# 477part.net
KiCad netlist of a schematic drawn in EAGLE
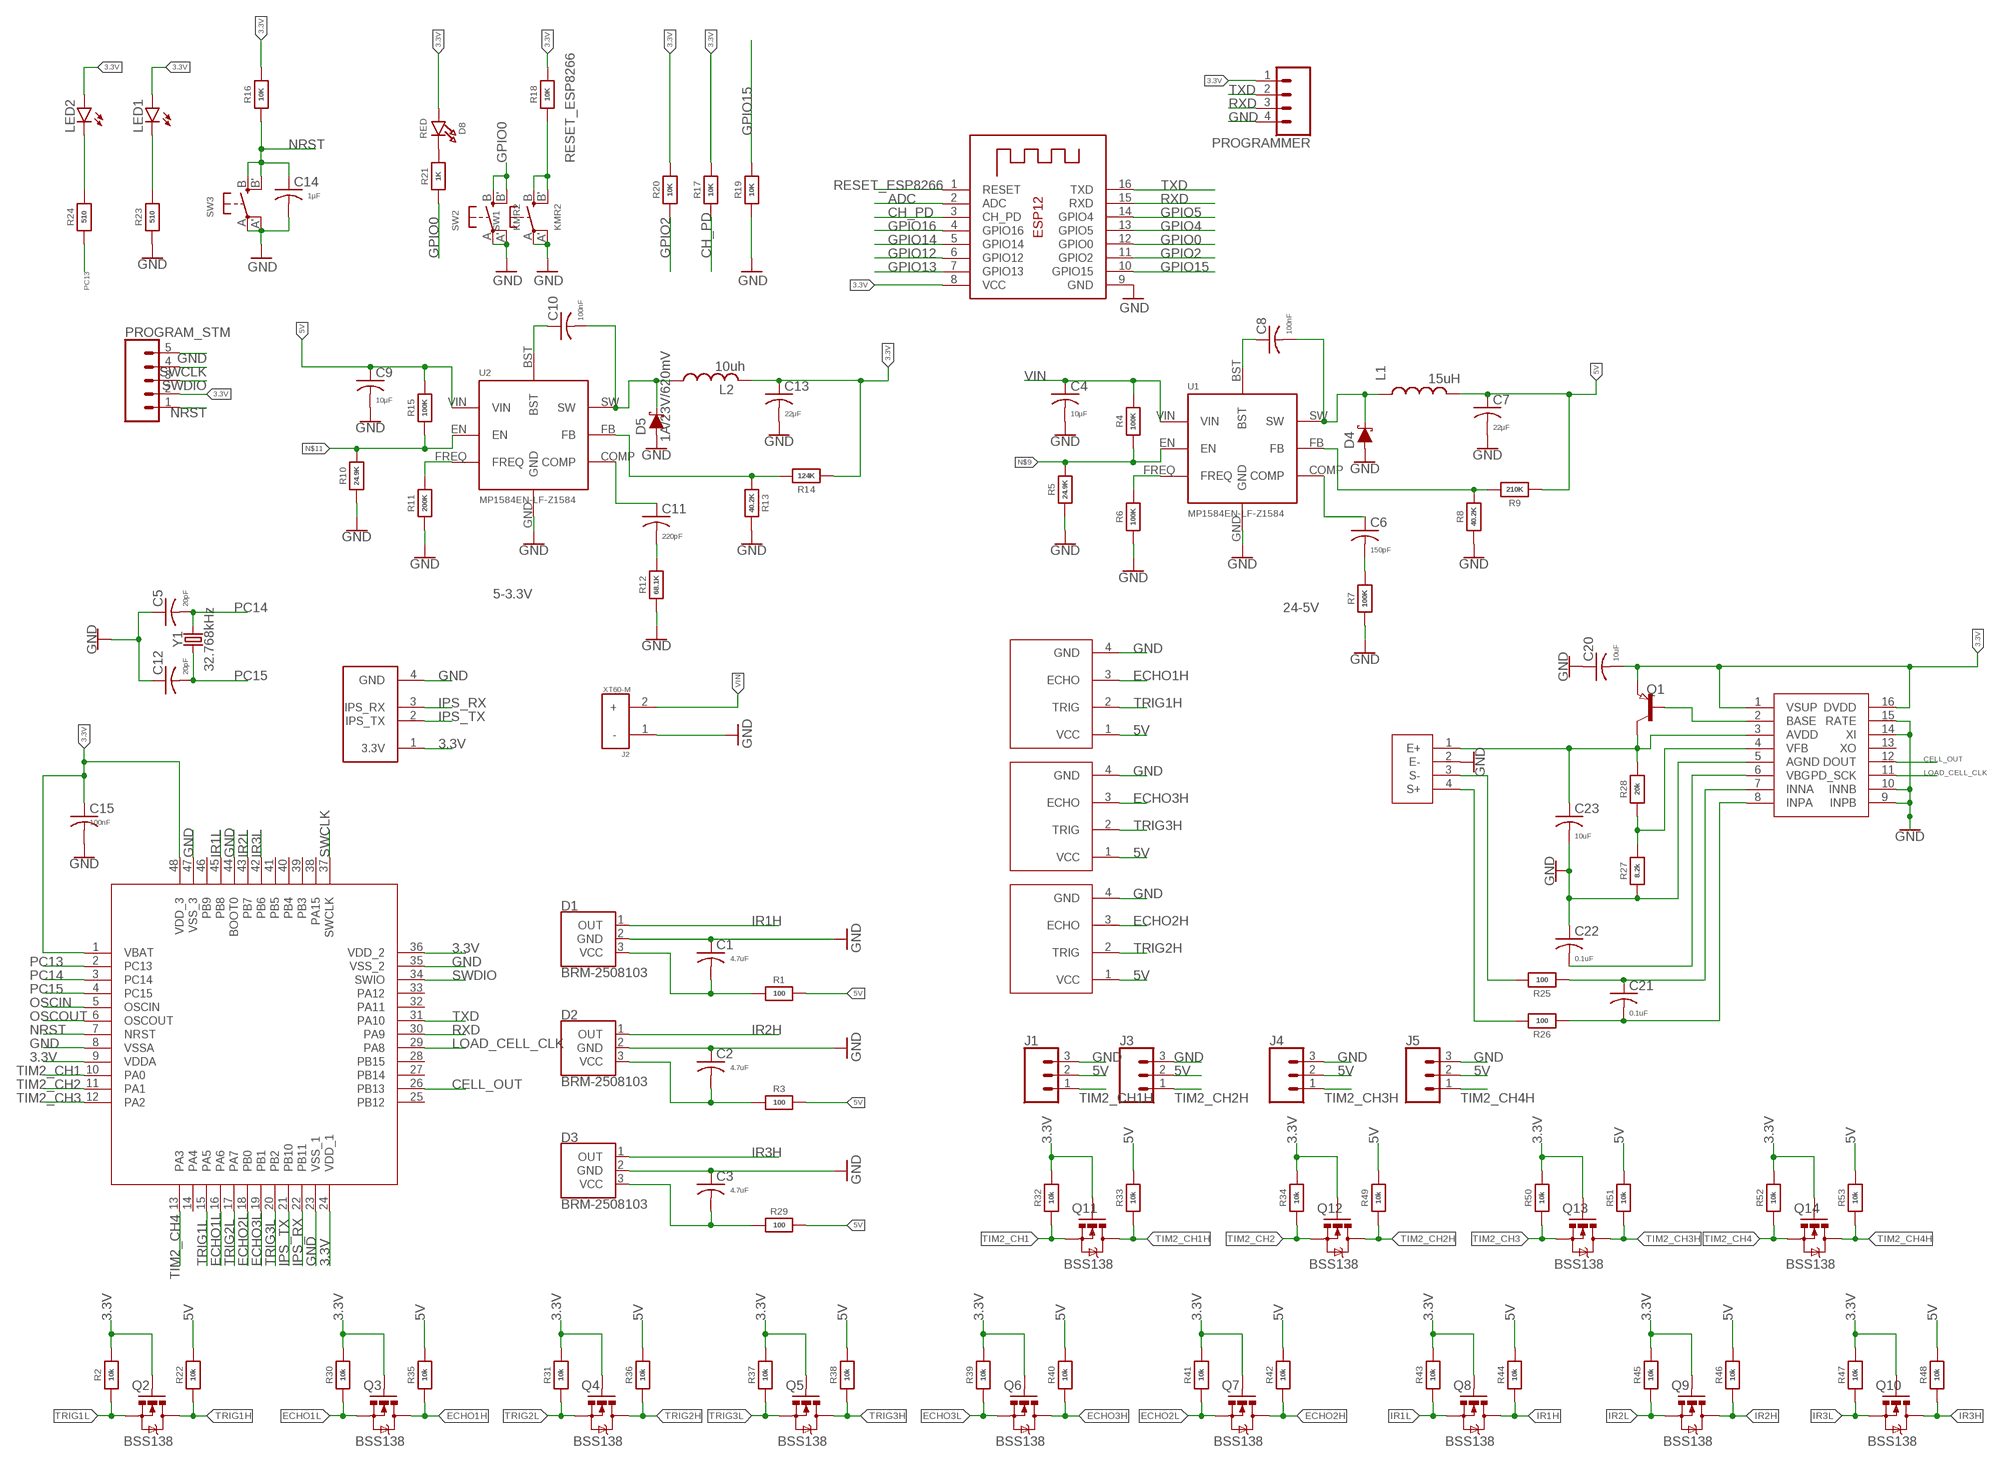
[diagram p0: schematic, sheet 1]

(export (version "E")
  (design (tool "Eeschema 10.0.6"))
  (components
    (comp (ref "C1")
      (value "4.7uF")
      (footprint "eagle-import:C0603")
      (libsource (lib "eagle-import") (part "C-USC0603"))
    )
    (comp (ref "C2")
      (value "4.7uF")
      (footprint "eagle-import:C0603")
      (libsource (lib "eagle-import") (part "C-USC0603"))
    )
    (comp (ref "C3")
      (value "4.7uF")
      (footprint "eagle-import:C0603")
      (libsource (lib "eagle-import") (part "C-USC0603"))
    )
    (comp (ref "C4")
      (value "10μF")
      (footprint "eagle-import:C0603")
      (libsource (lib "eagle-import") (part "C-USC0603"))
    )
    (comp (ref "C5")
      (value "20pF")
      (footprint "eagle-import:C0603")
      (libsource (lib "eagle-import") (part "C-USC0603"))
    )
    (comp (ref "C6")
      (value "150pF")
      (footprint "eagle-import:C0603")
      (libsource (lib "eagle-import") (part "C-USC0603"))
    )
    (comp (ref "C7")
      (value "22μF")
      (footprint "eagle-import:C0603")
      (libsource (lib "eagle-import") (part "C-USC0603"))
    )
    (comp (ref "C8")
      (value "100nF")
      (footprint "eagle-import:C0603")
      (libsource (lib "eagle-import") (part "C-USC0603"))
    )
    (comp (ref "C9")
      (value "10μF")
      (footprint "eagle-import:C0603")
      (libsource (lib "eagle-import") (part "C-USC0603"))
    )
    (comp (ref "C10")
      (value "100nF")
      (footprint "eagle-import:C0603")
      (libsource (lib "eagle-import") (part "C-USC0603"))
    )
    (comp (ref "C11")
      (value "220pF")
      (footprint "eagle-import:C0603")
      (libsource (lib "eagle-import") (part "C-USC0603"))
    )
    (comp (ref "C12")
      (value "20pF")
      (footprint "eagle-import:C0603")
      (libsource (lib "eagle-import") (part "C-USC0603"))
    )
    (comp (ref "C13")
      (value "22μF")
      (footprint "eagle-import:C0603")
      (libsource (lib "eagle-import") (part "C-USC0603"))
    )
    (comp (ref "C14")
      (value "1µF")
      (footprint "eagle-import:C0603")
      (libsource (lib "eagle-import") (part "C-USC0603"))
    )
    (comp (ref "C15")
      (value "100nF")
      (footprint "eagle-import:C0603")
      (libsource (lib "eagle-import") (part "C-USC0603"))
    )
    (comp (ref "C20")
      (value "10uF")
      (footprint "eagle-import:C0603")
      (libsource (lib "eagle-import") (part "C-USC0603"))
    )
    (comp (ref "C21")
      (value "0.1uF")
      (footprint "eagle-import:C0603")
      (libsource (lib "eagle-import") (part "C-USC0603"))
    )
    (comp (ref "C22")
      (value "0.1uF")
      (footprint "eagle-import:C0603")
      (libsource (lib "eagle-import") (part "C-USC0603"))
    )
    (comp (ref "C23")
      (value "10uF")
      (footprint "eagle-import:C0603")
      (libsource (lib "eagle-import") (part "C-USC0603"))
    )
    (comp (ref "D1")
      (value "BRM-2508103")
      (footprint "eagle-import:1X03")
      (libsource (lib "eagle-import") (part "BRM-2508103"))
    )
    (comp (ref "D2")
      (value "BRM-2508103")
      (footprint "eagle-import:1X03")
      (libsource (lib "eagle-import") (part "BRM-2508103"))
    )
    (comp (ref "D3")
      (value "BRM-2508103")
      (footprint "eagle-import:1X03")
      (libsource (lib "eagle-import") (part "BRM-2508103"))
    )
    (comp (ref "D4")
      (value "1A/23V/620mV")
      (footprint "eagle-import:SOD-323")
      (libsource (lib "eagle-import") (part "DIODE-SCHOTTKY-BAT20J"))
    )
    (comp (ref "D5")
      (value "1A/23V/620mV")
      (footprint "eagle-import:SOD-323")
      (libsource (lib "eagle-import") (part "DIODE-SCHOTTKY-BAT20J"))
    )
    (comp (ref "D8")
      (value "RED")
      (footprint "eagle-import:CHIPLED_0805_NOOUTLINE")
      (libsource (lib "eagle-import") (part "LED0805_NOOUTLINE"))
    )
    (comp (ref "ESP8266")
      (value "ESP-8266")
      (footprint "eagle-import:ESP-12")
      (libsource (lib "eagle-import") (part "ESP-12"))
    )
    (comp (ref "HC_SR04_1")
      (value "ULTRA_4")
      (footprint "eagle-import:1X04")
      (libsource (lib "eagle-import") (part "ULTRA_4"))
    )
    (comp (ref "HC_SR04_2")
      (value "ULTRA_4")
      (footprint "eagle-import:1X04")
      (libsource (lib "eagle-import") (part "ULTRA_4"))
    )
    (comp (ref "HC_SR04_3")
      (value "ULTRA_4")
      (footprint "eagle-import:1X04")
      (libsource (lib "eagle-import") (part "ULTRA_4"))
    )
    (comp (ref "J1")
      (value "CONN_03")
      (footprint "eagle-import:1X03")
      (libsource (lib "eagle-import") (part "CONN_03"))
    )
    (comp (ref "J2")
      (value "XT60-M")
      (footprint "eagle-import:AMASS_XT60-M")
      (fields (field (name "MF") "AMASS"))
      (libsource (lib "eagle-import") (part "XT60-M"))
    )
    (comp (ref "J3")
      (value "CONN_03")
      (footprint "eagle-import:1X03")
      (libsource (lib "eagle-import") (part "CONN_03"))
    )
    (comp (ref "J4")
      (value "CONN_03")
      (footprint "eagle-import:1X03")
      (libsource (lib "eagle-import") (part "CONN_03"))
    )
    (comp (ref "J5")
      (value "CONN_03")
      (footprint "eagle-import:1X03")
      (libsource (lib "eagle-import") (part "CONN_03"))
    )
    (comp (ref "L1")
      (value "15uH")
      (footprint "eagle-import:INDUCTOR2")
      (libsource (lib "eagle-import") (part "INDUCTOR2"))
    )
    (comp (ref "L2")
      (value "10uh")
      (footprint "eagle-import:INDUCTOR")
      (libsource (lib "eagle-import") (part "INDUCTOR"))
    )
    (comp (ref "LED1")
      (value "LEDCHIP-LED0603")
      (footprint "eagle-import:CHIP-LED0603")
      (libsource (lib "eagle-import") (part "LEDCHIP-LED0603"))
    )
    (comp (ref "LED2")
      (value "LEDCHIP-LED0603")
      (footprint "eagle-import:CHIP-LED0603")
      (libsource (lib "eagle-import") (part "LEDCHIP-LED0603"))
    )
    (comp (ref "PROGRAMMER")
      (value "CONN_04")
      (footprint "eagle-import:1X04")
      (libsource (lib "eagle-import") (part "CONN_04"))
    )
    (comp (ref "PROGRAM_STM")
      (value "CONN_05")
      (footprint "eagle-import:1X05")
      (libsource (lib "eagle-import") (part "CONN_05"))
    )
    (comp (ref "Q1")
      (value "PNP-TRANSISTOR_SOT23")
      (footprint "eagle-import:SOT23")
      (libsource (lib "eagle-import") (part "PNP-TRANSISTOR_SOT23"))
    )
    (comp (ref "Q2")
      (value "BSS138")
      (footprint "eagle-import:SOT23-3")
      (libsource (lib "eagle-import") (part "MOSFET-NCHANNELSMD"))
    )
    (comp (ref "Q3")
      (value "BSS138")
      (footprint "eagle-import:SOT23-3")
      (libsource (lib "eagle-import") (part "MOSFET-NCHANNELSMD"))
    )
    (comp (ref "Q4")
      (value "BSS138")
      (footprint "eagle-import:SOT23-3")
      (libsource (lib "eagle-import") (part "MOSFET-NCHANNELSMD"))
    )
    (comp (ref "Q5")
      (value "BSS138")
      (footprint "eagle-import:SOT23-3")
      (libsource (lib "eagle-import") (part "MOSFET-NCHANNELSMD"))
    )
    (comp (ref "Q6")
      (value "BSS138")
      (footprint "eagle-import:SOT23-3")
      (libsource (lib "eagle-import") (part "MOSFET-NCHANNELSMD"))
    )
    (comp (ref "Q7")
      (value "BSS138")
      (footprint "eagle-import:SOT23-3")
      (libsource (lib "eagle-import") (part "MOSFET-NCHANNELSMD"))
    )
    (comp (ref "Q8")
      (value "BSS138")
      (footprint "eagle-import:SOT23-3")
      (libsource (lib "eagle-import") (part "MOSFET-NCHANNELSMD"))
    )
    (comp (ref "Q9")
      (value "BSS138")
      (footprint "eagle-import:SOT23-3")
      (libsource (lib "eagle-import") (part "MOSFET-NCHANNELSMD"))
    )
    (comp (ref "Q10")
      (value "BSS138")
      (footprint "eagle-import:SOT23-3")
      (libsource (lib "eagle-import") (part "MOSFET-NCHANNELSMD"))
    )
    (comp (ref "Q11")
      (value "BSS138")
      (footprint "eagle-import:SOT23-3")
      (libsource (lib "eagle-import") (part "MOSFET-NCHANNELSMD"))
    )
    (comp (ref "Q12")
      (value "BSS138")
      (footprint "eagle-import:SOT23-3")
      (libsource (lib "eagle-import") (part "MOSFET-NCHANNELSMD"))
    )
    (comp (ref "Q13")
      (value "BSS138")
      (footprint "eagle-import:SOT23-3")
      (libsource (lib "eagle-import") (part "MOSFET-NCHANNELSMD"))
    )
    (comp (ref "Q14")
      (value "BSS138")
      (footprint "eagle-import:SOT23-3")
      (libsource (lib "eagle-import") (part "MOSFET-NCHANNELSMD"))
    )
    (comp (ref "R1")
      (value "100")
      (footprint "eagle-import:0805-NO")
      (libsource (lib "eagle-import") (part "RESISTOR0805_NOOUTLINE"))
    )
    (comp (ref "R2")
      (value "10k")
      (footprint "eagle-import:0805-NO")
      (libsource (lib "eagle-import") (part "RESISTOR0805_NOOUTLINE"))
    )
    (comp (ref "R3")
      (value "100")
      (footprint "eagle-import:0805-NO")
      (libsource (lib "eagle-import") (part "RESISTOR0805_NOOUTLINE"))
    )
    (comp (ref "R4")
      (value "100K")
      (footprint "eagle-import:0805-NO")
      (libsource (lib "eagle-import") (part "RESISTOR0805_NOOUTLINE"))
    )
    (comp (ref "R5")
      (value "24.9K")
      (footprint "eagle-import:0805-NO")
      (libsource (lib "eagle-import") (part "RESISTOR0805_NOOUTLINE"))
    )
    (comp (ref "R6")
      (value "100K")
      (footprint "eagle-import:0805-NO")
      (libsource (lib "eagle-import") (part "RESISTOR0805_NOOUTLINE"))
    )
    (comp (ref "R7")
      (value "100K")
      (footprint "eagle-import:0805-NO")
      (libsource (lib "eagle-import") (part "RESISTOR0805_NOOUTLINE"))
    )
    (comp (ref "R8")
      (value "40.2K")
      (footprint "eagle-import:0805-NO")
      (libsource (lib "eagle-import") (part "RESISTOR0805_NOOUTLINE"))
    )
    (comp (ref "R9")
      (value "210K")
      (footprint "eagle-import:0805-NO")
      (libsource (lib "eagle-import") (part "RESISTOR0805_NOOUTLINE"))
    )
    (comp (ref "R10")
      (value "24.9K")
      (footprint "eagle-import:0805-NO")
      (libsource (lib "eagle-import") (part "RESISTOR0805_NOOUTLINE"))
    )
    (comp (ref "R11")
      (value "200K")
      (footprint "eagle-import:0805-NO")
      (libsource (lib "eagle-import") (part "RESISTOR0805_NOOUTLINE"))
    )
    (comp (ref "R12")
      (value "68.1K")
      (footprint "eagle-import:0805-NO")
      (libsource (lib "eagle-import") (part "RESISTOR0805_NOOUTLINE"))
    )
    (comp (ref "R13")
      (value "40.2K")
      (footprint "eagle-import:0805-NO")
      (libsource (lib "eagle-import") (part "RESISTOR0805_NOOUTLINE"))
    )
    (comp (ref "R14")
      (value "124K")
      (footprint "eagle-import:0805-NO")
      (libsource (lib "eagle-import") (part "RESISTOR0805_NOOUTLINE"))
    )
    (comp (ref "R15")
      (value "100K")
      (footprint "eagle-import:0805-NO")
      (libsource (lib "eagle-import") (part "RESISTOR0805_NOOUTLINE"))
    )
    (comp (ref "R16")
      (value "10K")
      (footprint "eagle-import:0805-NO")
      (libsource (lib "eagle-import") (part "RESISTOR0805_NOOUTLINE"))
    )
    (comp (ref "R17")
      (value "10K")
      (footprint "eagle-import:0805-NO")
      (libsource (lib "eagle-import") (part "RESISTOR0805_NOOUTLINE"))
    )
    (comp (ref "R18")
      (value "10K")
      (footprint "eagle-import:0805-NO")
      (libsource (lib "eagle-import") (part "RESISTOR0805_NOOUTLINE"))
    )
    (comp (ref "R19")
      (value "10K")
      (footprint "eagle-import:0805-NO")
      (libsource (lib "eagle-import") (part "RESISTOR0805_NOOUTLINE"))
    )
    (comp (ref "R20")
      (value "10K")
      (footprint "eagle-import:0805-NO")
      (libsource (lib "eagle-import") (part "RESISTOR0805_NOOUTLINE"))
    )
    (comp (ref "R21")
      (value "1K")
      (footprint "eagle-import:0805-NO")
      (libsource (lib "eagle-import") (part "RESISTOR0805_NOOUTLINE"))
    )
    (comp (ref "R22")
      (value "10k")
      (footprint "eagle-import:0805-NO")
      (libsource (lib "eagle-import") (part "RESISTOR0805_NOOUTLINE"))
    )
    (comp (ref "R23")
      (value "510")
      (footprint "eagle-import:0805-NO")
      (libsource (lib "eagle-import") (part "RESISTOR0805_NOOUTLINE"))
    )
    (comp (ref "R24")
      (value "510")
      (footprint "eagle-import:0805-NO")
      (libsource (lib "eagle-import") (part "RESISTOR0805_NOOUTLINE"))
    )
    (comp (ref "R25")
      (value "100")
      (footprint "eagle-import:0805-NO")
      (libsource (lib "eagle-import") (part "RESISTOR0805_NOOUTLINE"))
    )
    (comp (ref "R26")
      (value "100")
      (footprint "eagle-import:0805-NO")
      (libsource (lib "eagle-import") (part "RESISTOR0805_NOOUTLINE"))
    )
    (comp (ref "R27")
      (value "8.2k")
      (footprint "eagle-import:0805-NO")
      (libsource (lib "eagle-import") (part "RESISTOR0805_NOOUTLINE"))
    )
    (comp (ref "R28")
      (value "20k")
      (footprint "eagle-import:0805-NO")
      (libsource (lib "eagle-import") (part "RESISTOR0805_NOOUTLINE"))
    )
    (comp (ref "R29")
      (value "100")
      (footprint "eagle-import:0805-NO")
      (libsource (lib "eagle-import") (part "RESISTOR0805_NOOUTLINE"))
    )
    (comp (ref "R30")
      (value "10k")
      (footprint "eagle-import:0805-NO")
      (libsource (lib "eagle-import") (part "RESISTOR0805_NOOUTLINE"))
    )
    (comp (ref "R31")
      (value "10k")
      (footprint "eagle-import:0805-NO")
      (libsource (lib "eagle-import") (part "RESISTOR0805_NOOUTLINE"))
    )
    (comp (ref "R32")
      (value "10k")
      (footprint "eagle-import:0805-NO")
      (libsource (lib "eagle-import") (part "RESISTOR0805_NOOUTLINE"))
    )
    (comp (ref "R33")
      (value "10k")
      (footprint "eagle-import:0805-NO")
      (libsource (lib "eagle-import") (part "RESISTOR0805_NOOUTLINE"))
    )
    (comp (ref "R34")
      (value "10k")
      (footprint "eagle-import:0805-NO")
      (libsource (lib "eagle-import") (part "RESISTOR0805_NOOUTLINE"))
    )
    (comp (ref "R35")
      (value "10k")
      (footprint "eagle-import:0805-NO")
      (libsource (lib "eagle-import") (part "RESISTOR0805_NOOUTLINE"))
    )
    (comp (ref "R36")
      (value "10k")
      (footprint "eagle-import:0805-NO")
      (libsource (lib "eagle-import") (part "RESISTOR0805_NOOUTLINE"))
    )
    (comp (ref "R37")
      (value "10k")
      (footprint "eagle-import:0805-NO")
      (libsource (lib "eagle-import") (part "RESISTOR0805_NOOUTLINE"))
    )
    (comp (ref "R38")
      (value "10k")
      (footprint "eagle-import:0805-NO")
      (libsource (lib "eagle-import") (part "RESISTOR0805_NOOUTLINE"))
    )
    (comp (ref "R39")
      (value "10k")
      (footprint "eagle-import:0805-NO")
      (libsource (lib "eagle-import") (part "RESISTOR0805_NOOUTLINE"))
    )
    (comp (ref "R40")
      (value "10k")
      (footprint "eagle-import:0805-NO")
      (libsource (lib "eagle-import") (part "RESISTOR0805_NOOUTLINE"))
    )
    (comp (ref "R41")
      (value "10k")
      (footprint "eagle-import:0805-NO")
      (libsource (lib "eagle-import") (part "RESISTOR0805_NOOUTLINE"))
    )
    (comp (ref "R42")
      (value "10k")
      (footprint "eagle-import:0805-NO")
      (libsource (lib "eagle-import") (part "RESISTOR0805_NOOUTLINE"))
    )
    (comp (ref "R43")
      (value "10k")
      (footprint "eagle-import:0805-NO")
      (libsource (lib "eagle-import") (part "RESISTOR0805_NOOUTLINE"))
    )
    (comp (ref "R44")
      (value "10k")
      (footprint "eagle-import:0805-NO")
      (libsource (lib "eagle-import") (part "RESISTOR0805_NOOUTLINE"))
    )
    (comp (ref "R45")
      (value "10k")
      (footprint "eagle-import:0805-NO")
      (libsource (lib "eagle-import") (part "RESISTOR0805_NOOUTLINE"))
    )
    (comp (ref "R46")
      (value "10k")
      (footprint "eagle-import:0805-NO")
      (libsource (lib "eagle-import") (part "RESISTOR0805_NOOUTLINE"))
    )
    (comp (ref "R47")
      (value "10k")
      (footprint "eagle-import:0805-NO")
      (libsource (lib "eagle-import") (part "RESISTOR0805_NOOUTLINE"))
    )
    (comp (ref "R48")
      (value "10k")
      (footprint "eagle-import:0805-NO")
      (libsource (lib "eagle-import") (part "RESISTOR0805_NOOUTLINE"))
    )
    (comp (ref "R49")
      (value "10k")
      (footprint "eagle-import:0805-NO")
      (libsource (lib "eagle-import") (part "RESISTOR0805_NOOUTLINE"))
    )
    (comp (ref "R50")
      (value "10k")
      (footprint "eagle-import:0805-NO")
      (libsource (lib "eagle-import") (part "RESISTOR0805_NOOUTLINE"))
    )
    (comp (ref "R51")
      (value "10k")
      (footprint "eagle-import:0805-NO")
      (libsource (lib "eagle-import") (part "RESISTOR0805_NOOUTLINE"))
    )
    (comp (ref "R52")
      (value "10k")
      (footprint "eagle-import:0805-NO")
      (libsource (lib "eagle-import") (part "RESISTOR0805_NOOUTLINE"))
    )
    (comp (ref "R53")
      (value "10k")
      (footprint "eagle-import:0805-NO")
      (libsource (lib "eagle-import") (part "RESISTOR0805_NOOUTLINE"))
    )
    (comp (ref "STM32F1")
      (value "STM32F1LQFP48")
      (footprint "eagle-import:LQFP-48")
      (libsource (lib "eagle-import") (part "STM32F1LQFP48"))
    )
    (comp (ref "SW1")
      (value "KMR2")
      (footprint "eagle-import:BTN_KMR2_4.6X2.8")
      (libsource (lib "eagle-import") (part "SWITCH_TACT_SMT4.6X2.8"))
    )
    (comp (ref "SW2")
      (value "KMR2")
      (footprint "eagle-import:BTN_KMR2_4.6X2.8")
      (libsource (lib "eagle-import") (part "SWITCH_TACT_SMT4.6X2.8"))
    )
    (comp (ref "SW3")
      (value "KMR2")
      (footprint "eagle-import:BTN_KMR2_4.6X2.8")
      (libsource (lib "eagle-import") (part "SWITCH_TACT_SMT4.6X2.8"))
    )
    (comp (ref "U$1")
      (value "IPS_G4")
      (footprint "eagle-import:1X04")
      (libsource (lib "eagle-import") (part "IPS_G4"))
    )
    (comp (ref "U$9")
      (value "FSR_SR")
      (footprint "eagle-import:1X04")
      (libsource (lib "eagle-import") (part "FSR_SR"))
    )
    (comp (ref "U$10")
      (value "HX711")
      (footprint "eagle-import:SO16A")
      (libsource (lib "eagle-import") (part "HX711"))
    )
    (comp (ref "U1")
      (value "MP1584EN-LF-Z1584")
      (footprint "eagle-import:MP1584_V2")
      (libsource (lib "eagle-import") (part "MP1584EN-LF-Z1584"))
    )
    (comp (ref "U2")
      (value "MP1584EN-LF-Z1584")
      (footprint "eagle-import:MP1584_V2")
      (libsource (lib "eagle-import") (part "MP1584EN-LF-Z1584"))
    )
    (comp (ref "Y1")
      (value "32.768kHz")
      (footprint "eagle-import:CRYSTAL-SMD-3.2X1.5MM")
      (libsource (lib "eagle-import") (part "CRYSTAL-32.768KHZSMD-3.2X1.5"))
    )
  )
  (nets
    (net (code "1") (name "/ADC") (class "Default")
      (node (ref "ESP8266") (pin "2") (pinfunction "ADC_2") (pintype "passive"))
    )
    (net (code "2") (name "/CELL_OUT") (class "Default")
      (node (ref "STM32F1") (pin "26") (pinfunction "PB13_26") (pintype "bidirectional"))
      (node (ref "U$10") (pin "12") (pinfunction "DOUT_12") (pintype "bidirectional"))
    )
    (net (code "3") (name "/CH_PD") (class "Default")
      (node (ref "ESP8266") (pin "3") (pinfunction "CH_PD_3") (pintype "input"))
      (node (ref "R17") (pin "1") (pinfunction "1_1") (pintype "passive"))
    )
    (net (code "4") (name "/GPIO0") (class "Default")
      (node (ref "ESP8266") (pin "12") (pinfunction "GPIO0_12") (pintype "bidirectional"))
      (node (ref "R21") (pin "1") (pinfunction "1_1") (pintype "passive"))
      (node (ref "SW2") (pin "B") (pinfunction "S_B") (pintype "passive"))
      (node (ref "SW2") (pin "B'") (pinfunction "S1_B'") (pintype "passive"))
    )
    (net (code "5") (name "/GPIO2") (class "Default")
      (node (ref "ESP8266") (pin "11") (pinfunction "GPIO2_11") (pintype "bidirectional"))
      (node (ref "R20") (pin "1") (pinfunction "1_1") (pintype "passive"))
    )
    (net (code "6") (name "/GPIO4") (class "Default")
      (node (ref "ESP8266") (pin "13") (pinfunction "GPIO5_13") (pintype "bidirectional"))
    )
    (net (code "7") (name "/GPIO5") (class "Default")
      (node (ref "ESP8266") (pin "14") (pinfunction "GPIO4_14") (pintype "bidirectional"))
    )
    (net (code "8") (name "/GPIO12") (class "Default")
      (node (ref "ESP8266") (pin "6") (pinfunction "GPIO12_6") (pintype "bidirectional"))
    )
    (net (code "9") (name "/GPIO13") (class "Default")
      (node (ref "ESP8266") (pin "7") (pinfunction "GPIO13_7") (pintype "bidirectional"))
    )
    (net (code "10") (name "/GPIO14") (class "Default")
      (node (ref "ESP8266") (pin "5") (pinfunction "GPIO14_5") (pintype "bidirectional"))
    )
    (net (code "11") (name "/GPIO15") (class "Default")
      (node (ref "ESP8266") (pin "10") (pinfunction "GPIO15_10") (pintype "bidirectional"))
      (node (ref "R19") (pin "2") (pinfunction "2_2") (pintype "passive"))
    )
    (net (code "12") (name "/GPIO16") (class "Default")
      (node (ref "ESP8266") (pin "4") (pinfunction "GPIO16_4") (pintype "bidirectional"))
    )
    (net (code "13") (name "/IPS_RX") (class "Default")
      (node (ref "STM32F1") (pin "22") (pinfunction "PB11_22") (pintype "bidirectional"))
      (node (ref "U$1") (pin "3") (pinfunction "IPS_RX_3") (pintype "bidirectional"))
    )
    (net (code "14") (name "/IPS_TX") (class "Default")
      (node (ref "STM32F1") (pin "21") (pinfunction "PB10_21") (pintype "bidirectional"))
      (node (ref "U$1") (pin "2") (pinfunction "IPS_TX_2") (pintype "bidirectional"))
    )
    (net (code "15") (name "/LOAD_CELL_CLK") (class "Default")
      (node (ref "STM32F1") (pin "29") (pinfunction "PA8_29") (pintype "bidirectional"))
      (node (ref "U$10") (pin "11") (pinfunction "PD_SCK_11") (pintype "bidirectional"))
    )
    (net (code "16") (name "/NRST") (class "Default")
      (node (ref "C14") (pin "1") (pinfunction "1_1") (pintype "passive"))
      (node (ref "PROGRAM_STM") (pin "1") (pinfunction "1_1") (pintype "passive"))
      (node (ref "R16") (pin "1") (pinfunction "1_1") (pintype "passive"))
      (node (ref "STM32F1") (pin "7") (pinfunction "NRST_7") (pintype "bidirectional"))
      (node (ref "SW3") (pin "B") (pinfunction "S_B") (pintype "passive"))
      (node (ref "SW3") (pin "B'") (pinfunction "S1_B'") (pintype "passive"))
    )
    (net (code "17") (name "/OSCIN") (class "Default")
      (node (ref "STM32F1") (pin "5") (pinfunction "OSCIN_5") (pintype "bidirectional"))
    )
    (net (code "18") (name "/OSCOUT") (class "Default")
      (node (ref "STM32F1") (pin "6") (pinfunction "OSCOUT_6") (pintype "bidirectional"))
    )
    (net (code "19") (name "/PC13") (class "Default")
      (node (ref "R24") (pin "1") (pinfunction "1_1") (pintype "passive"))
      (node (ref "STM32F1") (pin "2") (pinfunction "PC13_2") (pintype "bidirectional"))
    )
    (net (code "20") (name "/PC14") (class "Default")
      (node (ref "C5") (pin "2") (pinfunction "2_2") (pintype "passive"))
      (node (ref "STM32F1") (pin "3") (pinfunction "PC14_3") (pintype "bidirectional"))
      (node (ref "Y1") (pin "P$2") (pinfunction "2_P$2") (pintype "passive"))
    )
    (net (code "21") (name "/PC15") (class "Default")
      (node (ref "C12") (pin "2") (pinfunction "2_2") (pintype "passive"))
      (node (ref "STM32F1") (pin "4") (pinfunction "PC15_4") (pintype "bidirectional"))
      (node (ref "Y1") (pin "P$1") (pinfunction "1_P$1") (pintype "passive"))
    )
    (net (code "22") (name "/RESET_ESP8266") (class "Default")
      (node (ref "ESP8266") (pin "1") (pinfunction "RESET_1") (pintype "input"))
      (node (ref "R18") (pin "1") (pinfunction "1_1") (pintype "passive"))
      (node (ref "SW1") (pin "B") (pinfunction "S_B") (pintype "passive"))
      (node (ref "SW1") (pin "B'") (pinfunction "S1_B'") (pintype "passive"))
    )
    (net (code "23") (name "/RXD") (class "Default")
      (node (ref "ESP8266") (pin "15") (pinfunction "RXD_15") (pintype "input"))
      (node (ref "PROGRAMMER") (pin "3") (pinfunction "3_3") (pintype "passive"))
      (node (ref "STM32F1") (pin "30") (pinfunction "PA9_30") (pintype "bidirectional"))
    )
    (net (code "24") (name "/SWCLK") (class "Default")
      (node (ref "PROGRAM_STM") (pin "4") (pinfunction "4_4") (pintype "passive"))
      (node (ref "STM32F1") (pin "37") (pinfunction "SWCLK_37") (pintype "bidirectional"))
    )
    (net (code "25") (name "/SWDIO") (class "Default")
      (node (ref "PROGRAM_STM") (pin "3") (pinfunction "3_3") (pintype "passive"))
      (node (ref "STM32F1") (pin "34") (pinfunction "SWIO_34") (pintype "bidirectional"))
    )
    (net (code "26") (name "/TXD") (class "Default")
      (node (ref "ESP8266") (pin "16") (pinfunction "TXD_16") (pintype "output"))
      (node (ref "PROGRAMMER") (pin "2") (pinfunction "2_2") (pintype "passive"))
      (node (ref "STM32F1") (pin "31") (pinfunction "PA10_31") (pintype "bidirectional"))
    )
    (net (code "27") (name "3.3V") (class "Default")
      (node (ref "C13") (pin "1") (pinfunction "1_1") (pintype "passive"))
      (node (ref "C15") (pin "1") (pinfunction "1_1") (pintype "passive"))
      (node (ref "C20") (pin "2") (pinfunction "2_2") (pintype "passive"))
      (node (ref "D8") (pin "A") (pinfunction "A_A") (pintype "passive"))
      (node (ref "ESP8266") (pin "8") (pinfunction "VCC_8") (pintype "power_in"))
      (node (ref "L2") (pin "P$2") (pinfunction "2_P$2") (pintype "passive"))
      (node (ref "LED1") (pin "A") (pinfunction "A_A") (pintype "passive"))
      (node (ref "LED2") (pin "A") (pinfunction "A_A") (pintype "passive"))
      (node (ref "PROGRAMMER") (pin "1") (pinfunction "1_1") (pintype "passive"))
      (node (ref "PROGRAM_STM") (pin "2") (pinfunction "2_2") (pintype "passive"))
      (node (ref "Q1") (pin "2") (pinfunction "E_2") (pintype "passive"))
      (node (ref "Q10") (pin "1") (pinfunction "G_1") (pintype "passive"))
      (node (ref "Q11") (pin "1") (pinfunction "G_1") (pintype "passive"))
      (node (ref "Q12") (pin "1") (pinfunction "G_1") (pintype "passive"))
      (node (ref "Q13") (pin "1") (pinfunction "G_1") (pintype "passive"))
      (node (ref "Q14") (pin "1") (pinfunction "G_1") (pintype "passive"))
      (node (ref "Q2") (pin "1") (pinfunction "G_1") (pintype "passive"))
      (node (ref "Q3") (pin "1") (pinfunction "G_1") (pintype "passive"))
      (node (ref "Q4") (pin "1") (pinfunction "G_1") (pintype "passive"))
      (node (ref "Q5") (pin "1") (pinfunction "G_1") (pintype "passive"))
      (node (ref "Q6") (pin "1") (pinfunction "G_1") (pintype "passive"))
      (node (ref "Q7") (pin "1") (pinfunction "G_1") (pintype "passive"))
      (node (ref "Q8") (pin "1") (pinfunction "G_1") (pintype "passive"))
      (node (ref "Q9") (pin "1") (pinfunction "G_1") (pintype "passive"))
      (node (ref "R14") (pin "1") (pinfunction "1_1") (pintype "passive"))
      (node (ref "R16") (pin "2") (pinfunction "2_2") (pintype "passive"))
      (node (ref "R17") (pin "2") (pinfunction "2_2") (pintype "passive"))
      (node (ref "R18") (pin "2") (pinfunction "2_2") (pintype "passive"))
      (node (ref "R2") (pin "2") (pinfunction "2_2") (pintype "passive"))
      (node (ref "R20") (pin "2") (pinfunction "2_2") (pintype "passive"))
      (node (ref "R30") (pin "2") (pinfunction "2_2") (pintype "passive"))
      (node (ref "R31") (pin "2") (pinfunction "2_2") (pintype "passive"))
      (node (ref "R32") (pin "2") (pinfunction "2_2") (pintype "passive"))
      (node (ref "R34") (pin "2") (pinfunction "2_2") (pintype "passive"))
      (node (ref "R37") (pin "2") (pinfunction "2_2") (pintype "passive"))
      (node (ref "R39") (pin "2") (pinfunction "2_2") (pintype "passive"))
      (node (ref "R41") (pin "2") (pinfunction "2_2") (pintype "passive"))
      (node (ref "R43") (pin "2") (pinfunction "2_2") (pintype "passive"))
      (node (ref "R45") (pin "2") (pinfunction "2_2") (pintype "passive"))
      (node (ref "R47") (pin "2") (pinfunction "2_2") (pintype "passive"))
      (node (ref "R50") (pin "2") (pinfunction "2_2") (pintype "passive"))
      (node (ref "R52") (pin "2") (pinfunction "2_2") (pintype "passive"))
      (node (ref "STM32F1") (pin "1") (pinfunction "VBAT_1") (pintype "bidirectional"))
      (node (ref "STM32F1") (pin "24") (pinfunction "VDD_1_24") (pintype "bidirectional"))
      (node (ref "STM32F1") (pin "36") (pinfunction "VDD_2_36") (pintype "bidirectional"))
      (node (ref "STM32F1") (pin "48") (pinfunction "VDD_3_48") (pintype "bidirectional"))
      (node (ref "STM32F1") (pin "9") (pinfunction "VDDA_9") (pintype "bidirectional"))
      (node (ref "U$1") (pin "1") (pinfunction "3.3V_1") (pintype "bidirectional"))
      (node (ref "U$10") (pin "1") (pinfunction "VSUP_1") (pintype "bidirectional"))
      (node (ref "U$10") (pin "16") (pinfunction "DVDD_16") (pintype "bidirectional"))
    )
    (net (code "28") (name "5V") (class "Default")
      (node (ref "C7") (pin "1") (pinfunction "1_1") (pintype "passive"))
      (node (ref "C9") (pin "1") (pinfunction "1_1") (pintype "passive"))
      (node (ref "HC_SR04_1") (pin "1") (pinfunction "VCC_1") (pintype "bidirectional"))
      (node (ref "HC_SR04_2") (pin "1") (pinfunction "VCC_1") (pintype "bidirectional"))
      (node (ref "HC_SR04_3") (pin "1") (pinfunction "VCC_1") (pintype "bidirectional"))
      (node (ref "J1") (pin "2") (pinfunction "2_2") (pintype "passive"))
      (node (ref "J3") (pin "2") (pinfunction "2_2") (pintype "passive"))
      (node (ref "J4") (pin "2") (pinfunction "2_2") (pintype "passive"))
      (node (ref "J5") (pin "2") (pinfunction "2_2") (pintype "passive"))
      (node (ref "L1") (pin "P$2") (pinfunction "2_P$2") (pintype "passive"))
      (node (ref "R1") (pin "2") (pinfunction "2_2") (pintype "passive"))
      (node (ref "R15") (pin "2") (pinfunction "2_2") (pintype "passive"))
      (node (ref "R22") (pin "2") (pinfunction "2_2") (pintype "passive"))
      (node (ref "R29") (pin "2") (pinfunction "2_2") (pintype "passive"))
      (node (ref "R3") (pin "2") (pinfunction "2_2") (pintype "passive"))
      (node (ref "R33") (pin "2") (pinfunction "2_2") (pintype "passive"))
      (node (ref "R35") (pin "2") (pinfunction "2_2") (pintype "passive"))
      (node (ref "R36") (pin "2") (pinfunction "2_2") (pintype "passive"))
      (node (ref "R38") (pin "2") (pinfunction "2_2") (pintype "passive"))
      (node (ref "R40") (pin "2") (pinfunction "2_2") (pintype "passive"))
      (node (ref "R42") (pin "2") (pinfunction "2_2") (pintype "passive"))
      (node (ref "R44") (pin "2") (pinfunction "2_2") (pintype "passive"))
      (node (ref "R46") (pin "2") (pinfunction "2_2") (pintype "passive"))
      (node (ref "R48") (pin "2") (pinfunction "2_2") (pintype "passive"))
      (node (ref "R49") (pin "2") (pinfunction "2_2") (pintype "passive"))
      (node (ref "R51") (pin "2") (pinfunction "2_2") (pintype "passive"))
      (node (ref "R53") (pin "2") (pinfunction "2_2") (pintype "passive"))
      (node (ref "R9") (pin "1") (pinfunction "1_1") (pintype "passive"))
      (node (ref "U2") (pin "VIN") (pinfunction "VIN_VIN") (pintype "input"))
    )
    (net (code "29") (name "ECHO1H") (class "Default")
      (node (ref "HC_SR04_1") (pin "3") (pinfunction "ECHO_3") (pintype "bidirectional"))
      (node (ref "Q3") (pin "3") (pinfunction "D_3") (pintype "passive"))
      (node (ref "R35") (pin "1") (pinfunction "1_1") (pintype "passive"))
    )
    (net (code "30") (name "ECHO1L") (class "Default")
      (node (ref "Q3") (pin "2") (pinfunction "S_2") (pintype "passive"))
      (node (ref "R30") (pin "1") (pinfunction "1_1") (pintype "passive"))
      (node (ref "STM32F1") (pin "16") (pinfunction "PA6_16") (pintype "bidirectional"))
    )
    (net (code "31") (name "ECHO2H") (class "Default")
      (node (ref "HC_SR04_3") (pin "3") (pinfunction "ECHO_3") (pintype "bidirectional"))
      (node (ref "Q7") (pin "3") (pinfunction "D_3") (pintype "passive"))
      (node (ref "R42") (pin "1") (pinfunction "1_1") (pintype "passive"))
    )
    (net (code "32") (name "ECHO2L") (class "Default")
      (node (ref "Q7") (pin "2") (pinfunction "S_2") (pintype "passive"))
      (node (ref "R41") (pin "1") (pinfunction "1_1") (pintype "passive"))
      (node (ref "STM32F1") (pin "18") (pinfunction "PB0_18") (pintype "bidirectional"))
    )
    (net (code "33") (name "ECHO3H") (class "Default")
      (node (ref "HC_SR04_2") (pin "3") (pinfunction "ECHO_3") (pintype "bidirectional"))
      (node (ref "Q6") (pin "3") (pinfunction "D_3") (pintype "passive"))
      (node (ref "R40") (pin "1") (pinfunction "1_1") (pintype "passive"))
    )
    (net (code "34") (name "ECHO3L") (class "Default")
      (node (ref "Q6") (pin "2") (pinfunction "S_2") (pintype "passive"))
      (node (ref "R39") (pin "1") (pinfunction "1_1") (pintype "passive"))
      (node (ref "STM32F1") (pin "19") (pinfunction "PB1_19") (pintype "bidirectional"))
    )
    (net (code "35") (name "GND") (class "Default")
      (node (ref "C1") (pin "1") (pinfunction "1_1") (pintype "passive"))
      (node (ref "C12") (pin "1") (pinfunction "1_1") (pintype "passive"))
      (node (ref "C13") (pin "2") (pinfunction "2_2") (pintype "passive"))
      (node (ref "C14") (pin "2") (pinfunction "2_2") (pintype "passive"))
      (node (ref "C15") (pin "2") (pinfunction "2_2") (pintype "passive"))
      (node (ref "C2") (pin "1") (pinfunction "1_1") (pintype "passive"))
      (node (ref "C20") (pin "1") (pinfunction "1_1") (pintype "passive"))
      (node (ref "C22") (pin "1") (pinfunction "1_1") (pintype "passive"))
      (node (ref "C23") (pin "2") (pinfunction "2_2") (pintype "passive"))
      (node (ref "C3") (pin "1") (pinfunction "1_1") (pintype "passive"))
      (node (ref "C4") (pin "2") (pinfunction "2_2") (pintype "passive"))
      (node (ref "C5") (pin "1") (pinfunction "1_1") (pintype "passive"))
      (node (ref "C7") (pin "2") (pinfunction "2_2") (pintype "passive"))
      (node (ref "C9") (pin "2") (pinfunction "2_2") (pintype "passive"))
      (node (ref "D1") (pin "2") (pinfunction "GND_2") (pintype "bidirectional"))
      (node (ref "D2") (pin "2") (pinfunction "GND_2") (pintype "bidirectional"))
      (node (ref "D3") (pin "2") (pinfunction "GND_2") (pintype "bidirectional"))
      (node (ref "D4") (pin "A") (pinfunction "A_A") (pintype "passive"))
      (node (ref "D5") (pin "A") (pinfunction "A_A") (pintype "passive"))
      (node (ref "ESP8266") (pin "9") (pinfunction "GND_9") (pintype "power_in"))
      (node (ref "HC_SR04_1") (pin "4") (pinfunction "GND_4") (pintype "bidirectional"))
      (node (ref "HC_SR04_2") (pin "4") (pinfunction "GND_4") (pintype "bidirectional"))
      (node (ref "HC_SR04_3") (pin "4") (pinfunction "GND_4") (pintype "bidirectional"))
      (node (ref "J1") (pin "3") (pinfunction "3_3") (pintype "passive"))
      (node (ref "J2") (pin "1") (pinfunction "-_1") (pintype "passive"))
      (node (ref "J3") (pin "3") (pinfunction "3_3") (pintype "passive"))
      (node (ref "J4") (pin "3") (pinfunction "3_3") (pintype "passive"))
      (node (ref "J5") (pin "3") (pinfunction "3_3") (pintype "passive"))
      (node (ref "PROGRAMMER") (pin "4") (pinfunction "4_4") (pintype "passive"))
      (node (ref "PROGRAM_STM") (pin "5") (pinfunction "5_5") (pintype "passive"))
      (node (ref "R10") (pin "1") (pinfunction "1_1") (pintype "passive"))
      (node (ref "R11") (pin "1") (pinfunction "1_1") (pintype "passive"))
      (node (ref "R12") (pin "1") (pinfunction "1_1") (pintype "passive"))
      (node (ref "R13") (pin "2") (pinfunction "2_2") (pintype "passive"))
      (node (ref "R19") (pin "1") (pinfunction "1_1") (pintype "passive"))
      (node (ref "R23") (pin "1") (pinfunction "1_1") (pintype "passive"))
      (node (ref "R27") (pin "1") (pinfunction "1_1") (pintype "passive"))
      (node (ref "R5") (pin "1") (pinfunction "1_1") (pintype "passive"))
      (node (ref "R6") (pin "1") (pinfunction "1_1") (pintype "passive"))
      (node (ref "R7") (pin "1") (pinfunction "1_1") (pintype "passive"))
      (node (ref "R8") (pin "1") (pinfunction "1_1") (pintype "passive"))
      (node (ref "STM32F1") (pin "23") (pinfunction "VSS_1_23") (pintype "bidirectional"))
      (node (ref "STM32F1") (pin "35") (pinfunction "VSS_2_35") (pintype "bidirectional"))
      (node (ref "STM32F1") (pin "44") (pinfunction "BOOT0_44") (pintype "bidirectional"))
      (node (ref "STM32F1") (pin "47") (pinfunction "VSS_3_47") (pintype "bidirectional"))
      (node (ref "STM32F1") (pin "8") (pinfunction "VSSA_8") (pintype "bidirectional"))
      (node (ref "SW1") (pin "A") (pinfunction "P_A") (pintype "passive"))
      (node (ref "SW1") (pin "A'") (pinfunction "P1_A'") (pintype "passive"))
      (node (ref "SW2") (pin "A") (pinfunction "P_A") (pintype "passive"))
      (node (ref "SW2") (pin "A'") (pinfunction "P1_A'") (pintype "passive"))
      (node (ref "SW3") (pin "A") (pinfunction "P_A") (pintype "passive"))
      (node (ref "SW3") (pin "A'") (pinfunction "P1_A'") (pintype "passive"))
      (node (ref "U$1") (pin "4") (pinfunction "GND_4") (pintype "bidirectional"))
      (node (ref "U$10") (pin "10") (pinfunction "INNB_10") (pintype "bidirectional"))
      (node (ref "U$10") (pin "14") (pinfunction "XI_14") (pintype "bidirectional"))
      (node (ref "U$10") (pin "15") (pinfunction "RATE_15") (pintype "bidirectional"))
      (node (ref "U$10") (pin "5") (pinfunction "AGND_5") (pintype "bidirectional"))
      (node (ref "U$10") (pin "9") (pinfunction "INPB_9") (pintype "bidirectional"))
      (node (ref "U$9") (pin "2") (pinfunction "E-_2") (pintype "bidirectional"))
      (node (ref "U1") (pin "GND") (pinfunction "GND_GND") (pintype "power_in"))
      (node (ref "U2") (pin "GND") (pinfunction "GND_GND") (pintype "power_in"))
    )
    (net (code "36") (name "IR1H") (class "Default")
      (node (ref "D1") (pin "1") (pinfunction "OUT_1") (pintype "bidirectional"))
      (node (ref "Q8") (pin "3") (pinfunction "D_3") (pintype "passive"))
      (node (ref "R44") (pin "1") (pinfunction "1_1") (pintype "passive"))
    )
    (net (code "37") (name "IR1L") (class "Default")
      (node (ref "Q8") (pin "2") (pinfunction "S_2") (pintype "passive"))
      (node (ref "R43") (pin "1") (pinfunction "1_1") (pintype "passive"))
      (node (ref "STM32F1") (pin "45") (pinfunction "PB8_45") (pintype "bidirectional"))
    )
    (net (code "38") (name "IR2H") (class "Default")
      (node (ref "D2") (pin "1") (pinfunction "OUT_1") (pintype "bidirectional"))
      (node (ref "Q9") (pin "3") (pinfunction "D_3") (pintype "passive"))
      (node (ref "R46") (pin "1") (pinfunction "1_1") (pintype "passive"))
    )
    (net (code "39") (name "IR2L") (class "Default")
      (node (ref "Q9") (pin "2") (pinfunction "S_2") (pintype "passive"))
      (node (ref "R45") (pin "1") (pinfunction "1_1") (pintype "passive"))
      (node (ref "STM32F1") (pin "43") (pinfunction "PB7_43") (pintype "bidirectional"))
    )
    (net (code "40") (name "IR3H") (class "Default")
      (node (ref "D3") (pin "1") (pinfunction "OUT_1") (pintype "bidirectional"))
      (node (ref "Q10") (pin "3") (pinfunction "D_3") (pintype "passive"))
      (node (ref "R48") (pin "1") (pinfunction "1_1") (pintype "passive"))
    )
    (net (code "41") (name "IR3L") (class "Default")
      (node (ref "Q10") (pin "2") (pinfunction "S_2") (pintype "passive"))
      (node (ref "R47") (pin "1") (pinfunction "1_1") (pintype "passive"))
      (node (ref "STM32F1") (pin "42") (pinfunction "PB6_42") (pintype "bidirectional"))
    )
    (net (code "42") (name "N$9") (class "Default")
      (node (ref "R4") (pin "1") (pinfunction "1_1") (pintype "passive"))
      (node (ref "R5") (pin "2") (pinfunction "2_2") (pintype "passive"))
      (node (ref "U1") (pin "EN") (pinfunction "EN_EN") (pintype "input"))
    )
    (net (code "43") (name "N$11") (class "Default")
      (node (ref "R10") (pin "2") (pinfunction "2_2") (pintype "passive"))
      (node (ref "R15") (pin "1") (pinfunction "1_1") (pintype "passive"))
      (node (ref "U2") (pin "EN") (pinfunction "EN_EN") (pintype "input"))
    )
    (net (code "44") (name "Net-(C6-Pad1)") (class "Default")
      (node (ref "C6") (pin "1") (pinfunction "1_1") (pintype "passive"))
      (node (ref "U1") (pin "COMP") (pinfunction "COMP_COMP") (pintype "passive"))
    )
    (net (code "45") (name "Net-(C6-Pad2)") (class "Default")
      (node (ref "C6") (pin "2") (pinfunction "2_2") (pintype "passive"))
      (node (ref "R7") (pin "2") (pinfunction "2_2") (pintype "passive"))
    )
    (net (code "46") (name "Net-(C8-Pad1)") (class "Default")
      (node (ref "C8") (pin "1") (pinfunction "1_1") (pintype "passive"))
      (node (ref "U1") (pin "BST") (pinfunction "BST_BST") (pintype "passive"))
    )
    (net (code "47") (name "Net-(C10-Pad1)") (class "Default")
      (node (ref "C10") (pin "1") (pinfunction "1_1") (pintype "passive"))
      (node (ref "U2") (pin "BST") (pinfunction "BST_BST") (pintype "passive"))
    )
    (net (code "48") (name "Net-(C11-Pad1)") (class "Default")
      (node (ref "C11") (pin "1") (pinfunction "1_1") (pintype "passive"))
      (node (ref "U2") (pin "COMP") (pinfunction "COMP_COMP") (pintype "passive"))
    )
    (net (code "49") (name "Net-(C11-Pad2)") (class "Default")
      (node (ref "C11") (pin "2") (pinfunction "2_2") (pintype "passive"))
      (node (ref "R12") (pin "2") (pinfunction "2_2") (pintype "passive"))
    )
    (net (code "50") (name "Net-(D1-VCC)") (class "Default")
      (node (ref "C1") (pin "2") (pinfunction "2_2") (pintype "passive"))
      (node (ref "D1") (pin "3") (pinfunction "VCC_3") (pintype "bidirectional"))
      (node (ref "R1") (pin "1") (pinfunction "1_1") (pintype "passive"))
    )
    (net (code "51") (name "Net-(D2-VCC)") (class "Default")
      (node (ref "C2") (pin "2") (pinfunction "2_2") (pintype "passive"))
      (node (ref "D2") (pin "3") (pinfunction "VCC_3") (pintype "bidirectional"))
      (node (ref "R3") (pin "1") (pinfunction "1_1") (pintype "passive"))
    )
    (net (code "52") (name "Net-(D3-VCC)") (class "Default")
      (node (ref "C3") (pin "2") (pinfunction "2_2") (pintype "passive"))
      (node (ref "D3") (pin "3") (pinfunction "VCC_3") (pintype "bidirectional"))
      (node (ref "R29") (pin "1") (pinfunction "1_1") (pintype "passive"))
    )
    (net (code "53") (name "Net-(D8-PadC)") (class "Default")
      (node (ref "D8") (pin "C") (pinfunction "C_C") (pintype "passive"))
      (node (ref "R21") (pin "2") (pinfunction "2_2") (pintype "passive"))
    )
    (net (code "54") (name "Net-(L1-1)") (class "Default")
      (node (ref "C8") (pin "2") (pinfunction "2_2") (pintype "passive"))
      (node (ref "D4") (pin "C") (pinfunction "C_C") (pintype "passive"))
      (node (ref "L1") (pin "P$1") (pinfunction "1_P$1") (pintype "passive"))
      (node (ref "U1") (pin "SW") (pinfunction "SW_SW") (pintype "output"))
    )
    (net (code "55") (name "Net-(L2-1)") (class "Default")
      (node (ref "C10") (pin "2") (pinfunction "2_2") (pintype "passive"))
      (node (ref "D5") (pin "C") (pinfunction "C_C") (pintype "passive"))
      (node (ref "L2") (pin "P$1") (pinfunction "1_P$1") (pintype "passive"))
      (node (ref "U2") (pin "SW") (pinfunction "SW_SW") (pintype "output"))
    )
    (net (code "56") (name "Net-(LED1-PadC)") (class "Default")
      (node (ref "LED1") (pin "C") (pinfunction "C_C") (pintype "passive"))
      (node (ref "R23") (pin "2") (pinfunction "2_2") (pintype "passive"))
    )
    (net (code "57") (name "Net-(LED2-PadC)") (class "Default")
      (node (ref "LED2") (pin "C") (pinfunction "C_C") (pintype "passive"))
      (node (ref "R24") (pin "2") (pinfunction "2_2") (pintype "passive"))
    )
    (net (code "58") (name "Net-(Q1-B)") (class "Default")
      (node (ref "Q1") (pin "1") (pinfunction "B_1") (pintype "passive"))
      (node (ref "U$10") (pin "2") (pinfunction "BASE_2") (pintype "bidirectional"))
    )
    (net (code "59") (name "Net-(Q1-C)") (class "Default")
      (node (ref "C23") (pin "1") (pinfunction "1_1") (pintype "passive"))
      (node (ref "Q1") (pin "3") (pinfunction "C_3") (pintype "passive"))
      (node (ref "R28") (pin "2") (pinfunction "2_2") (pintype "passive"))
      (node (ref "U$10") (pin "3") (pinfunction "AVDD_3") (pintype "bidirectional"))
      (node (ref "U$9") (pin "1") (pinfunction "E+_1") (pintype "bidirectional"))
    )
    (net (code "60") (name "Net-(R6-Pad2)") (class "Default")
      (node (ref "R6") (pin "2") (pinfunction "2_2") (pintype "passive"))
      (node (ref "U1") (pin "FREQ") (pinfunction "FREQ_FREQ") (pintype "passive"))
    )
    (net (code "61") (name "Net-(R8-Pad2)") (class "Default")
      (node (ref "R8") (pin "2") (pinfunction "2_2") (pintype "passive"))
      (node (ref "R9") (pin "2") (pinfunction "2_2") (pintype "passive"))
      (node (ref "U1") (pin "FB") (pinfunction "FB_FB") (pintype "input"))
    )
    (net (code "62") (name "Net-(R11-Pad2)") (class "Default")
      (node (ref "R11") (pin "2") (pinfunction "2_2") (pintype "passive"))
      (node (ref "U2") (pin "FREQ") (pinfunction "FREQ_FREQ") (pintype "passive"))
    )
    (net (code "63") (name "Net-(R13-Pad1)") (class "Default")
      (node (ref "R13") (pin "1") (pinfunction "1_1") (pintype "passive"))
      (node (ref "R14") (pin "2") (pinfunction "2_2") (pintype "passive"))
      (node (ref "U2") (pin "FB") (pinfunction "FB_FB") (pintype "input"))
    )
    (net (code "64") (name "Net-(U$9-S+)") (class "Default")
      (node (ref "R26") (pin "2") (pinfunction "2_2") (pintype "passive"))
      (node (ref "U$9") (pin "4") (pinfunction "S+_4") (pintype "bidirectional"))
    )
    (net (code "65") (name "Net-(U$9-S-)") (class "Default")
      (node (ref "R25") (pin "2") (pinfunction "2_2") (pintype "passive"))
      (node (ref "U$9") (pin "3") (pinfunction "S-_3") (pintype "bidirectional"))
    )
    (net (code "66") (name "Net-(U$10-INNA)") (class "Default")
      (node (ref "C21") (pin "1") (pinfunction "1_1") (pintype "passive"))
      (node (ref "R25") (pin "1") (pinfunction "1_1") (pintype "passive"))
      (node (ref "U$10") (pin "7") (pinfunction "INNA_7") (pintype "bidirectional"))
    )
    (net (code "67") (name "Net-(U$10-INPA)") (class "Default")
      (node (ref "C21") (pin "2") (pinfunction "2_2") (pintype "passive"))
      (node (ref "R26") (pin "1") (pinfunction "1_1") (pintype "passive"))
      (node (ref "U$10") (pin "8") (pinfunction "INPA_8") (pintype "bidirectional"))
    )
    (net (code "68") (name "Net-(U$10-VBG)") (class "Default")
      (node (ref "C22") (pin "2") (pinfunction "2_2") (pintype "passive"))
      (node (ref "U$10") (pin "6") (pinfunction "VBG_6") (pintype "bidirectional"))
    )
    (net (code "69") (name "Net-(U$10-VFB)") (class "Default")
      (node (ref "R27") (pin "2") (pinfunction "2_2") (pintype "passive"))
      (node (ref "R28") (pin "1") (pinfunction "1_1") (pintype "passive"))
      (node (ref "U$10") (pin "4") (pinfunction "VFB_4") (pintype "bidirectional"))
    )
    (net (code "70") (name "TIM2_CH1") (class "Default")
      (node (ref "Q11") (pin "2") (pinfunction "S_2") (pintype "passive"))
      (node (ref "R32") (pin "1") (pinfunction "1_1") (pintype "passive"))
      (node (ref "STM32F1") (pin "10") (pinfunction "PA0_10") (pintype "bidirectional"))
    )
    (net (code "71") (name "TIM2_CH1H") (class "Default")
      (node (ref "J1") (pin "1") (pinfunction "1_1") (pintype "passive"))
      (node (ref "Q11") (pin "3") (pinfunction "D_3") (pintype "passive"))
      (node (ref "R33") (pin "1") (pinfunction "1_1") (pintype "passive"))
    )
    (net (code "72") (name "TIM2_CH2") (class "Default")
      (node (ref "Q12") (pin "2") (pinfunction "S_2") (pintype "passive"))
      (node (ref "R34") (pin "1") (pinfunction "1_1") (pintype "passive"))
      (node (ref "STM32F1") (pin "11") (pinfunction "PA1_11") (pintype "bidirectional"))
    )
    (net (code "73") (name "TIM2_CH2H") (class "Default")
      (node (ref "J3") (pin "1") (pinfunction "1_1") (pintype "passive"))
      (node (ref "Q12") (pin "3") (pinfunction "D_3") (pintype "passive"))
      (node (ref "R49") (pin "1") (pinfunction "1_1") (pintype "passive"))
    )
    (net (code "74") (name "TIM2_CH3") (class "Default")
      (node (ref "Q13") (pin "2") (pinfunction "S_2") (pintype "passive"))
      (node (ref "R50") (pin "1") (pinfunction "1_1") (pintype "passive"))
      (node (ref "STM32F1") (pin "12") (pinfunction "PA2_12") (pintype "bidirectional"))
    )
    (net (code "75") (name "TIM2_CH3H") (class "Default")
      (node (ref "J4") (pin "1") (pinfunction "1_1") (pintype "passive"))
      (node (ref "Q13") (pin "3") (pinfunction "D_3") (pintype "passive"))
      (node (ref "R51") (pin "1") (pinfunction "1_1") (pintype "passive"))
    )
    (net (code "76") (name "TIM2_CH4") (class "Default")
      (node (ref "Q14") (pin "2") (pinfunction "S_2") (pintype "passive"))
      (node (ref "R52") (pin "1") (pinfunction "1_1") (pintype "passive"))
      (node (ref "STM32F1") (pin "13") (pinfunction "PA3_13") (pintype "bidirectional"))
    )
    (net (code "77") (name "TIM2_CH4H") (class "Default")
      (node (ref "J5") (pin "1") (pinfunction "1_1") (pintype "passive"))
      (node (ref "Q14") (pin "3") (pinfunction "D_3") (pintype "passive"))
      (node (ref "R53") (pin "1") (pinfunction "1_1") (pintype "passive"))
    )
    (net (code "78") (name "TRIG1H") (class "Default")
      (node (ref "HC_SR04_1") (pin "2") (pinfunction "TRIG_2") (pintype "bidirectional"))
      (node (ref "Q2") (pin "3") (pinfunction "D_3") (pintype "passive"))
      (node (ref "R22") (pin "1") (pinfunction "1_1") (pintype "passive"))
    )
    (net (code "79") (name "TRIG1L") (class "Default")
      (node (ref "Q2") (pin "2") (pinfunction "S_2") (pintype "passive"))
      (node (ref "R2") (pin "1") (pinfunction "1_1") (pintype "passive"))
      (node (ref "STM32F1") (pin "15") (pinfunction "PA5_15") (pintype "bidirectional"))
    )
    (net (code "80") (name "TRIG2H") (class "Default")
      (node (ref "HC_SR04_3") (pin "2") (pinfunction "TRIG_2") (pintype "bidirectional"))
      (node (ref "Q4") (pin "3") (pinfunction "D_3") (pintype "passive"))
      (node (ref "R36") (pin "1") (pinfunction "1_1") (pintype "passive"))
    )
    (net (code "81") (name "TRIG2L") (class "Default")
      (node (ref "Q4") (pin "2") (pinfunction "S_2") (pintype "passive"))
      (node (ref "R31") (pin "1") (pinfunction "1_1") (pintype "passive"))
      (node (ref "STM32F1") (pin "17") (pinfunction "PA7_17") (pintype "bidirectional"))
    )
    (net (code "82") (name "TRIG3H") (class "Default")
      (node (ref "HC_SR04_2") (pin "2") (pinfunction "TRIG_2") (pintype "bidirectional"))
      (node (ref "Q5") (pin "3") (pinfunction "D_3") (pintype "passive"))
      (node (ref "R38") (pin "1") (pinfunction "1_1") (pintype "passive"))
    )
    (net (code "83") (name "TRIG3L") (class "Default")
      (node (ref "Q5") (pin "2") (pinfunction "S_2") (pintype "passive"))
      (node (ref "R37") (pin "1") (pinfunction "1_1") (pintype "passive"))
      (node (ref "STM32F1") (pin "20") (pinfunction "PB2_20") (pintype "bidirectional"))
    )
    (net (code "84") (name "VIN") (class "Default")
      (node (ref "C4") (pin "1") (pinfunction "1_1") (pintype "passive"))
      (node (ref "J2") (pin "2") (pinfunction "+_2") (pintype "passive"))
      (node (ref "R4") (pin "2") (pinfunction "2_2") (pintype "passive"))
      (node (ref "U1") (pin "VIN") (pinfunction "VIN_VIN") (pintype "input"))
    )
    (net (code "85") (name "unconnected-(STM32F1-PA4-Pad14)") (class "Default")
      (node (ref "STM32F1") (pin "14") (pinfunction "PA4_14") (pintype "bidirectional"))
    )
    (net (code "86") (name "unconnected-(STM32F1-PA11-Pad32)") (class "Default")
      (node (ref "STM32F1") (pin "32") (pinfunction "PA11_32") (pintype "bidirectional"))
    )
    (net (code "87") (name "unconnected-(STM32F1-PA12-Pad33)") (class "Default")
      (node (ref "STM32F1") (pin "33") (pinfunction "PA12_33") (pintype "bidirectional"))
    )
    (net (code "88") (name "unconnected-(STM32F1-PA15-Pad38)") (class "Default")
      (node (ref "STM32F1") (pin "38") (pinfunction "PA15_38") (pintype "bidirectional"))
    )
    (net (code "89") (name "unconnected-(STM32F1-PB3-Pad39)") (class "Default")
      (node (ref "STM32F1") (pin "39") (pinfunction "PB3_39") (pintype "bidirectional"))
    )
    (net (code "90") (name "unconnected-(STM32F1-PB4-Pad40)") (class "Default")
      (node (ref "STM32F1") (pin "40") (pinfunction "PB4_40") (pintype "bidirectional"))
    )
    (net (code "91") (name "unconnected-(STM32F1-PB5-Pad41)") (class "Default")
      (node (ref "STM32F1") (pin "41") (pinfunction "PB5_41") (pintype "bidirectional"))
    )
    (net (code "92") (name "unconnected-(STM32F1-PB9-Pad46)") (class "Default")
      (node (ref "STM32F1") (pin "46") (pinfunction "PB9_46") (pintype "bidirectional"))
    )
    (net (code "93") (name "unconnected-(STM32F1-PB12-Pad25)") (class "Default")
      (node (ref "STM32F1") (pin "25") (pinfunction "PB12_25") (pintype "bidirectional"))
    )
    (net (code "94") (name "unconnected-(STM32F1-PB14-Pad27)") (class "Default")
      (node (ref "STM32F1") (pin "27") (pinfunction "PB14_27") (pintype "bidirectional"))
    )
    (net (code "95") (name "unconnected-(STM32F1-PB15-Pad28)") (class "Default")
      (node (ref "STM32F1") (pin "28") (pinfunction "PB15_28") (pintype "bidirectional"))
    )
    (net (code "96") (name "unconnected-(U$10-XO-Pad13)") (class "Default")
      (node (ref "U$10") (pin "13") (pinfunction "XO_13") (pintype "bidirectional"))
    )
  )
)
